# tetris_nosound.net
KiCad netlist of a schematic drawn in EAGLE
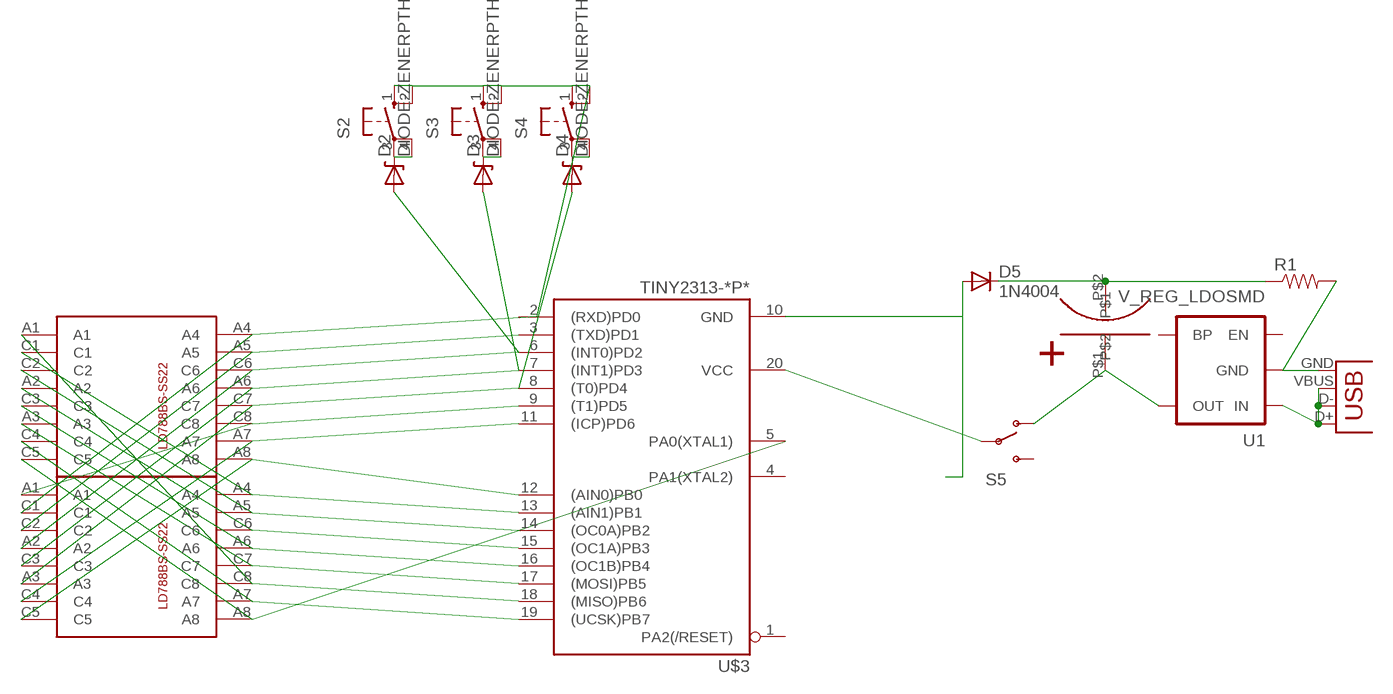
[diagram p0: schematic, sheet 1]

(export (version "E")
  (design (tool "Eeschema 10.0.6"))
  (components
    (comp (ref "D2")
      (value "DIODE-ZENERPTH")
      (footprint "eagle-import:DIODE-ZENER")
      (libsource (lib "eagle-import") (part "DIODE-ZENERPTH"))
    )
    (comp (ref "D3")
      (value "DIODE-ZENERPTH")
      (footprint "eagle-import:DIODE-ZENER")
      (libsource (lib "eagle-import") (part "DIODE-ZENERPTH"))
    )
    (comp (ref "D4")
      (value "DIODE-ZENERPTH")
      (footprint "eagle-import:DIODE-ZENER")
      (libsource (lib "eagle-import") (part "DIODE-ZENERPTH"))
    )
    (comp (ref "D5")
      (value "1N4004")
      (footprint "eagle-import:DO41-10")
      (libsource (lib "eagle-import") (part "1N4004"))
    )
    (comp (ref "R1")
      (value "RESISTORPTH1")
      (footprint "eagle-import:AXIAL-0.3")
      (libsource (lib "eagle-import") (part "RESISTORPTH1"))
    )
    (comp (ref "S2")
      (value "10-XX")
      (footprint "eagle-import:B3F-10XX")
      (fields (field (name "MPN") "B3F-1000"))
      (libsource (lib "eagle-import") (part "10-XX"))
    )
    (comp (ref "S3")
      (value "10-XX")
      (footprint "eagle-import:B3F-10XX")
      (fields (field (name "MPN") "B3F-1000"))
      (libsource (lib "eagle-import") (part "10-XX"))
    )
    (comp (ref "S4")
      (value "10-XX")
      (footprint "eagle-import:B3F-10XX")
      (fields (field (name "MPN") "B3F-1000"))
      (libsource (lib "eagle-import") (part "10-XX"))
    )
    (comp (ref "S5")
      (value "SWITCH-SPSTSMD2")
      (footprint "eagle-import:SWITCH-SPDT-SMD")
      (libsource (lib "eagle-import") (part "SWITCH-SPSTSMD2"))
    )
    (comp (ref "U$1")
      (value "LD788BS-SS22")
      (footprint "eagle-import:LD788BS-SS22")
      (libsource (lib "eagle-import") (part "LD788BS-SS22"))
    )
    (comp (ref "U$2")
      (value "LD788BS-SS22")
      (footprint "eagle-import:LD788BS-SS22")
      (libsource (lib "eagle-import") (part "LD788BS-SS22"))
    )
    (comp (ref "U$3")
      (value "TINY2313-*P*")
      (footprint "eagle-import:DIL20")
      (libsource (lib "eagle-import") (part "TINY2313-P"))
    )
    (comp (ref "U$5")
      (value "NICHICON_12F")
      (footprint "eagle-import:NICHICON_10X30")
      (libsource (lib "eagle-import") (part "NICHICON_12F"))
    )
    (comp (ref "U1")
      (value "V_REG_LDOSMD")
      (footprint "eagle-import:SOT23-5")
      (libsource (lib "eagle-import") (part "V_REG_LDOSMD"))
    )
    (comp (ref "X1")
      (value "USB-MICROB")
      (footprint "eagle-import:USB-MICROB")
      (libsource (lib "eagle-import") (part "USB-MICROB"))
    )
  )
  (nets
    (net (code "1") (name "Net-(D2-A)") (class "Default")
      (node (ref "D2") (pin "P$2") (pinfunction "A_P$2") (pintype "passive"))
      (node (ref "U$1") (pin "A2") (pinfunction "A2_A2") (pintype "bidirectional"))
      (node (ref "U$2") (pin "C6") (pinfunction "C6_C6") (pintype "bidirectional"))
      (node (ref "U$3") (pin "6") (pinfunction "(INT0)PD2_6") (pintype "bidirectional"))
    )
    (net (code "2") (name "Net-(D2-C)") (class "Default")
      (node (ref "D2") (pin "P$1") (pinfunction "C_P$1") (pintype "passive"))
      (node (ref "S2") (pin "3") (pinfunction "P_3") (pintype "passive"))
      (node (ref "S2") (pin "4") (pinfunction "P1_4") (pintype "passive"))
    )
    (net (code "3") (name "Net-(D3-A)") (class "Default")
      (node (ref "D3") (pin "P$2") (pinfunction "A_P$2") (pintype "passive"))
      (node (ref "U$1") (pin "C3") (pinfunction "C3_C3") (pintype "bidirectional"))
      (node (ref "U$2") (pin "A6") (pinfunction "A6_A6") (pintype "bidirectional"))
      (node (ref "U$3") (pin "7") (pinfunction "(INT1)PD3_7") (pintype "bidirectional"))
    )
    (net (code "4") (name "Net-(D3-C)") (class "Default")
      (node (ref "D3") (pin "P$1") (pinfunction "C_P$1") (pintype "passive"))
      (node (ref "S3") (pin "3") (pinfunction "P_3") (pintype "passive"))
      (node (ref "S3") (pin "4") (pinfunction "P1_4") (pintype "passive"))
    )
    (net (code "5") (name "Net-(D4-A)") (class "Default")
      (node (ref "D4") (pin "P$2") (pinfunction "A_P$2") (pintype "passive"))
      (node (ref "U$1") (pin "A3") (pinfunction "A3_A3") (pintype "bidirectional"))
      (node (ref "U$2") (pin "C7") (pinfunction "C7_C7") (pintype "bidirectional"))
      (node (ref "U$3") (pin "8") (pinfunction "(T0)PD4_8") (pintype "bidirectional"))
    )
    (net (code "6") (name "Net-(D4-C)") (class "Default")
      (node (ref "D4") (pin "P$1") (pinfunction "C_P$1") (pintype "passive"))
      (node (ref "S4") (pin "3") (pinfunction "P_3") (pintype "passive"))
      (node (ref "S4") (pin "4") (pinfunction "P1_4") (pintype "passive"))
    )
    (net (code "7") (name "Net-(R1-1)") (class "Default")
      (node (ref "D5") (pin "C") (pinfunction "C_C") (pintype "passive"))
      (node (ref "R1") (pin "P$1") (pinfunction "1_P$1") (pintype "passive"))
      (node (ref "U$5") (pin "P$2") (pinfunction "P$2_P$2") (pintype "bidirectional"))
    )
    (net (code "8") (name "Net-(R1-2)") (class "Default")
      (node (ref "R1") (pin "P$2") (pinfunction "2_P$2") (pintype "passive"))
      (node (ref "U1") (pin "2") (pinfunction "GND_2") (pintype "input"))
      (node (ref "X1") (pin "GND") (pinfunction "GND_GND") (pintype "bidirectional"))
    )
    (net (code "9") (name "Net-(S2-S)") (class "Default")
      (node (ref "S2") (pin "1") (pinfunction "S_1") (pintype "passive"))
      (node (ref "S2") (pin "2") (pinfunction "S1_2") (pintype "passive"))
      (node (ref "S3") (pin "1") (pinfunction "S_1") (pintype "passive"))
      (node (ref "S3") (pin "2") (pinfunction "S1_2") (pintype "passive"))
      (node (ref "S4") (pin "1") (pinfunction "S_1") (pintype "passive"))
      (node (ref "S4") (pin "2") (pinfunction "S1_2") (pintype "passive"))
      (node (ref "U$1") (pin "C1") (pinfunction "C1_C1") (pintype "bidirectional"))
      (node (ref "U$2") (pin "A4") (pinfunction "A4_A4") (pintype "bidirectional"))
    )
    (net (code "10") (name "Net-(S5-O)") (class "Default")
      (node (ref "S5") (pin "1") (pinfunction "O_1") (pintype "passive"))
      (node (ref "U$5") (pin "P$1") (pinfunction "P$1_P$1") (pintype "bidirectional"))
      (node (ref "U1") (pin "5") (pinfunction "OUT_5") (pintype "passive"))
    )
    (net (code "11") (name "Net-(S5-P)") (class "Default")
      (node (ref "S5") (pin "2") (pinfunction "P_2") (pintype "passive"))
      (node (ref "U$3") (pin "20") (pinfunction "VCC_20") (pintype "power_in"))
    )
    (net (code "12") (name "Net-(U$3-(AIN0)PB0)") (class "Default")
      (node (ref "U$1") (pin "C5") (pinfunction "C5_C5") (pintype "bidirectional"))
      (node (ref "U$2") (pin "A8") (pinfunction "A8_A8") (pintype "bidirectional"))
      (node (ref "U$3") (pin "12") (pinfunction "(AIN0)PB0_12") (pintype "bidirectional"))
    )
    (net (code "13") (name "Net-(U$3-(AIN1)PB1)") (class "Default")
      (node (ref "U$1") (pin "A4") (pinfunction "A4_A4") (pintype "bidirectional"))
      (node (ref "U$2") (pin "C1") (pinfunction "C1_C1") (pintype "bidirectional"))
      (node (ref "U$3") (pin "13") (pinfunction "(AIN1)PB1_13") (pintype "bidirectional"))
    )
    (net (code "14") (name "Net-(U$3-(ICP)PD6)") (class "Default")
      (node (ref "U$1") (pin "C4") (pinfunction "C4_C4") (pintype "bidirectional"))
      (node (ref "U$2") (pin "A7") (pinfunction "A7_A7") (pintype "bidirectional"))
      (node (ref "U$3") (pin "11") (pinfunction "(ICP)PD6_11") (pintype "bidirectional"))
    )
    (net (code "15") (name "Net-(U$3-(MISO)PB6)") (class "Default")
      (node (ref "U$1") (pin "C8") (pinfunction "C8_C8") (pintype "bidirectional"))
      (node (ref "U$2") (pin "A1") (pinfunction "A1_A1") (pintype "bidirectional"))
      (node (ref "U$3") (pin "18") (pinfunction "(MISO)PB6_18") (pintype "bidirectional"))
    )
    (net (code "16") (name "Net-(U$3-(MOSI)PB5)") (class "Default")
      (node (ref "U$1") (pin "C7") (pinfunction "C7_C7") (pintype "bidirectional"))
      (node (ref "U$2") (pin "A3") (pinfunction "A3_A3") (pintype "bidirectional"))
      (node (ref "U$3") (pin "17") (pinfunction "(MOSI)PB5_17") (pintype "bidirectional"))
    )
    (net (code "17") (name "Net-(U$3-(OC0A)PB2)") (class "Default")
      (node (ref "U$1") (pin "A5") (pinfunction "A5_A5") (pintype "bidirectional"))
      (node (ref "U$2") (pin "C2") (pinfunction "C2_C2") (pintype "bidirectional"))
      (node (ref "U$3") (pin "14") (pinfunction "(OC0A)PB2_14") (pintype "bidirectional"))
    )
    (net (code "18") (name "Net-(U$3-(OC1A)PB3)") (class "Default")
      (node (ref "U$1") (pin "C6") (pinfunction "C6_C6") (pintype "bidirectional"))
      (node (ref "U$2") (pin "A2") (pinfunction "A2_A2") (pintype "bidirectional"))
      (node (ref "U$3") (pin "15") (pinfunction "(OC1A)PB3_15") (pintype "bidirectional"))
    )
    (net (code "19") (name "Net-(U$3-(OC1B)PB4)") (class "Default")
      (node (ref "U$1") (pin "A6") (pinfunction "A6_A6") (pintype "bidirectional"))
      (node (ref "U$2") (pin "C3") (pinfunction "C3_C3") (pintype "bidirectional"))
      (node (ref "U$3") (pin "16") (pinfunction "(OC1B)PB4_16") (pintype "bidirectional"))
    )
    (net (code "20") (name "Net-(U$3-(T1)PD5)") (class "Default")
      (node (ref "U$1") (pin "A1") (pinfunction "A1_A1") (pintype "bidirectional"))
      (node (ref "U$2") (pin "C8") (pinfunction "C8_C8") (pintype "bidirectional"))
      (node (ref "U$3") (pin "9") (pinfunction "(T1)PD5_9") (pintype "bidirectional"))
    )
    (net (code "21") (name "Net-(U$3-(TXD)PD1)") (class "Default")
      (node (ref "U$1") (pin "C2") (pinfunction "C2_C2") (pintype "bidirectional"))
      (node (ref "U$2") (pin "A5") (pinfunction "A5_A5") (pintype "bidirectional"))
      (node (ref "U$3") (pin "3") (pinfunction "(TXD)PD1_3") (pintype "bidirectional"))
    )
    (net (code "22") (name "Net-(U$3-(UCSK)PB7)") (class "Default")
      (node (ref "U$1") (pin "A7") (pinfunction "A7_A7") (pintype "bidirectional"))
      (node (ref "U$2") (pin "C4") (pinfunction "C4_C4") (pintype "bidirectional"))
      (node (ref "U$3") (pin "19") (pinfunction "(UCSK)PB7_19") (pintype "bidirectional"))
    )
    (net (code "23") (name "Net-(U$3-GND)") (class "Default")
      (node (ref "D5") (pin "A") (pinfunction "A_A") (pintype "passive"))
      (node (ref "U$3") (pin "10") (pinfunction "GND_10") (pintype "power_in"))
    )
    (net (code "24") (name "Net-(U$3-PA0(XTAL1))") (class "Default")
      (node (ref "U$1") (pin "A8") (pinfunction "A8_A8") (pintype "bidirectional"))
      (node (ref "U$2") (pin "C5") (pinfunction "C5_C5") (pintype "bidirectional"))
      (node (ref "U$3") (pin "5") (pinfunction "PA0(XTAL1)_5") (pintype "bidirectional"))
    )
    (net (code "25") (name "Net-(U1-IN)") (class "Default")
      (node (ref "U1") (pin "1") (pinfunction "IN_1") (pintype "input"))
      (node (ref "X1") (pin "D+") (pinfunction "D+_D+") (pintype "bidirectional"))
      (node (ref "X1") (pin "D-") (pinfunction "D-_D-") (pintype "bidirectional"))
      (node (ref "X1") (pin "VBUS") (pinfunction "VBUS_VBUS") (pintype "bidirectional"))
    )
    (net (code "26") (name "unconnected-(S5-S-Pad3)") (class "Default")
      (node (ref "S5") (pin "3") (pinfunction "S_3") (pintype "passive"))
    )
    (net (code "27") (name "unconnected-(U$3-(RXD)PD0-Pad2)") (class "Default")
      (node (ref "U$3") (pin "2") (pinfunction "(RXD)PD0_2") (pintype "bidirectional"))
    )
    (net (code "28") (name "unconnected-(U$3-PA1(XTAL2)-Pad4)") (class "Default")
      (node (ref "U$3") (pin "4") (pinfunction "PA1(XTAL2)_4") (pintype "bidirectional"))
    )
    (net (code "29") (name "unconnected-(U$3-PA2({slash}RESET)-Pad1)") (class "Default")
      (node (ref "U$3") (pin "1") (pinfunction "PA2(/RESET)_1") (pintype "input"))
    )
    (net (code "30") (name "unconnected-(U1-BP-Pad4)") (class "Default")
      (node (ref "U1") (pin "4") (pinfunction "BP_4") (pintype "input"))
    )
    (net (code "31") (name "unconnected-(U1-EN-Pad3)") (class "Default")
      (node (ref "U1") (pin "3") (pinfunction "EN_3") (pintype "input"))
    )
  )
)
